# CarteTxCapteurDistance_2.net
KiCad netlist of a schematic drawn in Altium Designer
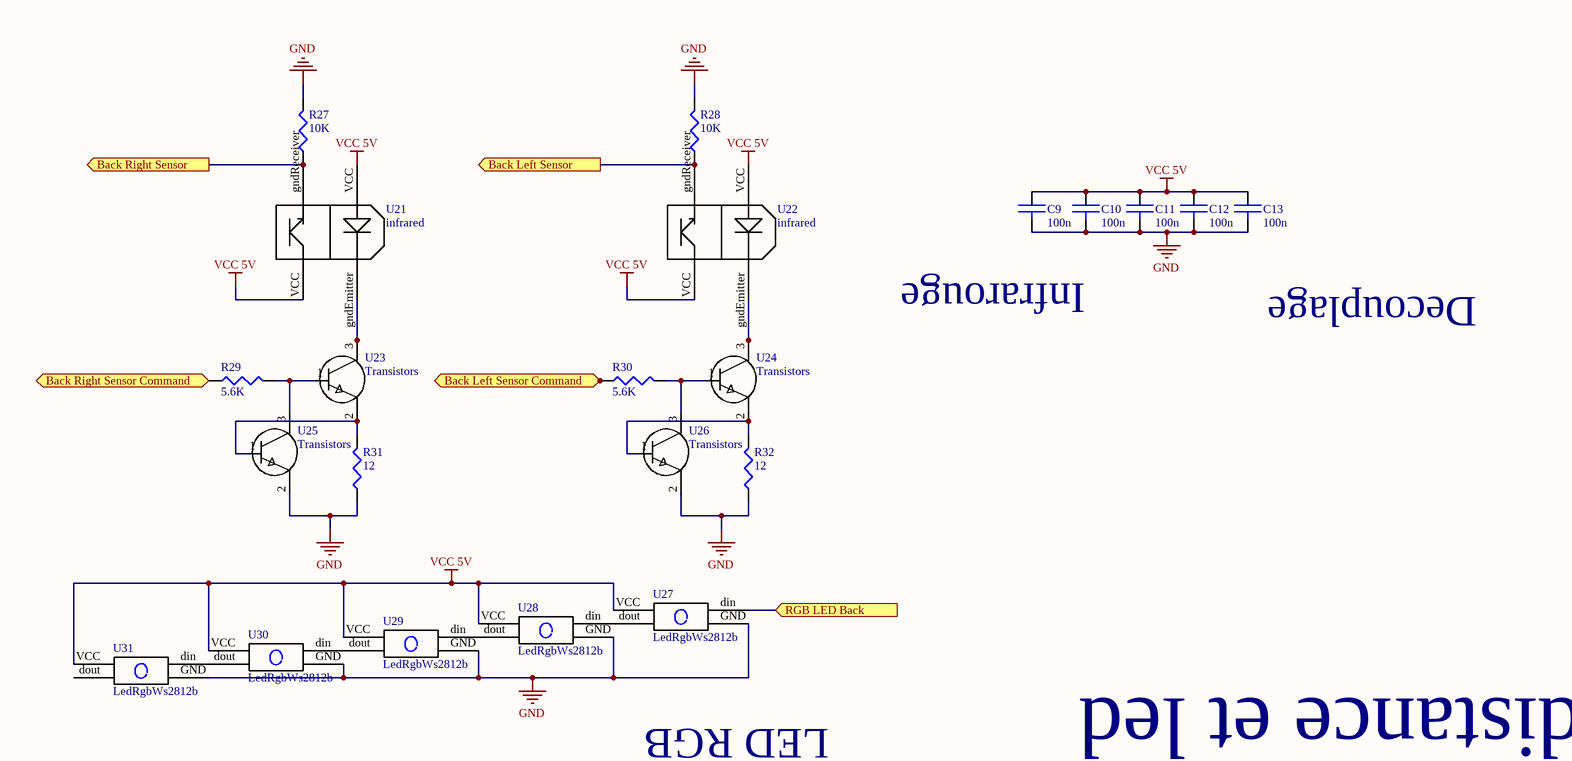
[diagram p0: CarteTxCapteurDistance 2.SchDoc, left]
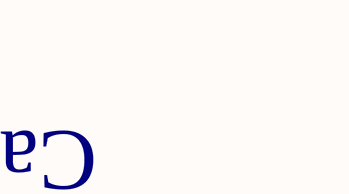
[diagram p1: CarteTxCapteurDistance 2.SchDoc, right]

(export (version "E")
  (design (tool "Eeschema 10.0.6"))
  (components
    (comp (ref "C9")
      (value "100n")
      (footprint "0805")
      (description "capacité non polarisée")
      (fields (field (name "Comment") "CAP"))
      (libsource (lib "ISEN_basics_26-05-2015") (part "CAP"))
    )
    (comp (ref "C10")
      (value "100n")
      (footprint "0805")
      (description "capacité non polarisée")
      (fields (field (name "Comment") "CAP"))
      (libsource (lib "ISEN_basics_26-05-2015") (part "CAP"))
    )
    (comp (ref "C11")
      (value "100n")
      (footprint "0805")
      (description "capacité non polarisée")
      (fields (field (name "Comment") "CAP"))
      (libsource (lib "ISEN_basics_26-05-2015") (part "CAP"))
    )
    (comp (ref "C12")
      (value "100n")
      (footprint "0805")
      (description "capacité non polarisée")
      (fields (field (name "Comment") "CAP"))
      (libsource (lib "ISEN_basics_26-05-2015") (part "CAP"))
    )
    (comp (ref "C13")
      (value "100n")
      (footprint "0805")
      (description "capacité non polarisée")
      (fields (field (name "Comment") "CAP"))
      (libsource (lib "ISEN_basics_26-05-2015") (part "CAP"))
    )
    (comp (ref "R27")
      (value "10K")
      (footprint "0805")
      (description "resistance")
      (fields (field (name "Comment") "RES"))
      (libsource (lib "ISEN_basics_26-05-2015") (part "RES"))
    )
    (comp (ref "R28")
      (value "10K")
      (footprint "0805")
      (description "resistance")
      (fields (field (name "Comment") "RES"))
      (libsource (lib "ISEN_basics_26-05-2015") (part "RES"))
    )
    (comp (ref "R29")
      (value "5.6K")
      (footprint "0805")
      (description "resistance")
      (fields (field (name "Comment") "RES"))
      (libsource (lib "ISEN_basics_26-05-2015") (part "RES"))
    )
    (comp (ref "R30")
      (value "5.6K")
      (footprint "0805")
      (description "resistance")
      (fields (field (name "Comment") "RES"))
      (libsource (lib "ISEN_basics_26-05-2015") (part "RES"))
    )
    (comp (ref "R31")
      (value "12")
      (footprint "0805")
      (description "resistance")
      (fields (field (name "Comment") "RES"))
      (libsource (lib "ISEN_basics_26-05-2015") (part "RES"))
    )
    (comp (ref "R32")
      (value "12")
      (footprint "0805")
      (description "resistance")
      (fields (field (name "Comment") "RES"))
      (libsource (lib "ISEN_basics_26-05-2015") (part "RES"))
    )
    (comp (ref "U21")
      (value "infrared")
      (footprint "Infrared")
      (libsource (lib "infrared") (part "RPR-359F"))
    )
    (comp (ref "U22")
      (value "infrared")
      (footprint "Infrared")
      (libsource (lib "infrared") (part "RPR-359F"))
    )
    (comp (ref "U23")
      (value "Transistors")
      (footprint "BC817-40")
      (description "NPN transistor")
      (libsource (lib "Transistors") (part "Transistors"))
    )
    (comp (ref "U24")
      (value "Transistors")
      (footprint "BC817-40")
      (description "NPN transistor")
      (libsource (lib "Transistors") (part "Transistors"))
    )
    (comp (ref "U25")
      (value "Transistors")
      (footprint "BC817-40")
      (description "NPN transistor")
      (libsource (lib "Transistors") (part "Transistors"))
    )
    (comp (ref "U26")
      (value "Transistors")
      (footprint "BC817-40")
      (description "NPN transistor")
      (libsource (lib "Transistors") (part "Transistors"))
    )
    (comp (ref "U27")
      (value "LedRgbWs2812b")
      (footprint "LedRgbWs2812b")
      (libsource (lib "LedRgbWs2812b") (part "LedRgbWs2812b"))
    )
    (comp (ref "U28")
      (value "LedRgbWs2812b")
      (footprint "LedRgbWs2812b")
      (libsource (lib "LedRgbWs2812b") (part "LedRgbWs2812b"))
    )
    (comp (ref "U29")
      (value "LedRgbWs2812b")
      (footprint "LedRgbWs2812b")
      (libsource (lib "LedRgbWs2812b") (part "LedRgbWs2812b"))
    )
    (comp (ref "U30")
      (value "LedRgbWs2812b")
      (footprint "LedRgbWs2812b")
      (libsource (lib "LedRgbWs2812b") (part "LedRgbWs2812b"))
    )
    (comp (ref "U31")
      (value "LedRgbWs2812b")
      (footprint "LedRgbWs2812b")
      (libsource (lib "LedRgbWs2812b") (part "LedRgbWs2812b"))
    )
  )
  (nets
    (net (code "1") (name "/Back Left Sensor") (class "Default")
      (node (ref "R28") (pin "1") (pintype "passive"))
      (node (ref "U22") (pin "gndReceiver") (pinfunction "gndReceiver_gndReceiver") (pintype "passive"))
    )
    (net (code "2") (name "/Back Left Sensor Command") (class "Default")
      (node (ref "R30") (pin "1") (pintype "passive"))
    )
    (net (code "3") (name "/Back Right Sensor") (class "Default")
      (node (ref "R27") (pin "1") (pintype "passive"))
      (node (ref "U21") (pin "gndReceiver") (pinfunction "gndReceiver_gndReceiver") (pintype "passive"))
    )
    (net (code "4") (name "/Back Right Sensor Command") (class "Default")
      (node (ref "R29") (pin "1") (pintype "passive"))
    )
    (net (code "5") (name "/RGB LED Back") (class "Default")
      (node (ref "U27") (pin "din") (pinfunction "din_din") (pintype "passive"))
    )
    (net (code "6") (name "GND") (class "Default")
      (node (ref "C10") (pin "2") (pinfunction "2_2") (pintype "passive"))
      (node (ref "C11") (pin "2") (pinfunction "2_2") (pintype "passive"))
      (node (ref "C12") (pin "2") (pinfunction "2_2") (pintype "passive"))
      (node (ref "C13") (pin "2") (pinfunction "2_2") (pintype "passive"))
      (node (ref "C9") (pin "2") (pinfunction "2_2") (pintype "passive"))
      (node (ref "R27") (pin "2") (pintype "passive"))
      (node (ref "R28") (pin "2") (pintype "passive"))
      (node (ref "R31") (pin "1") (pintype "passive"))
      (node (ref "R32") (pin "1") (pintype "passive"))
      (node (ref "U25") (pin "2") (pinfunction "Emi_2") (pintype "passive"))
      (node (ref "U26") (pin "2") (pinfunction "Emi_2") (pintype "passive"))
      (node (ref "U27") (pin "GND") (pinfunction "GND_GND") (pintype "passive"))
      (node (ref "U28") (pin "GND") (pinfunction "GND_GND") (pintype "passive"))
      (node (ref "U29") (pin "GND") (pinfunction "GND_GND") (pintype "passive"))
      (node (ref "U30") (pin "GND") (pinfunction "GND_GND") (pintype "passive"))
      (node (ref "U31") (pin "GND") (pinfunction "GND_GND") (pintype "passive"))
    )
    (net (code "7") (name "Net-(U23-Base)") (class "Default")
      (node (ref "R29") (pin "2") (pintype "passive"))
      (node (ref "U23") (pin "1") (pinfunction "Base_1") (pintype "passive"))
      (node (ref "U25") (pin "3") (pinfunction "Co_3") (pintype "passive"))
    )
    (net (code "8") (name "Net-(U23-Co)") (class "Default")
      (node (ref "U21") (pin "gndEmitter") (pinfunction "gndEmitter_gndEmitter") (pintype "passive"))
      (node (ref "U23") (pin "3") (pinfunction "Co_3") (pintype "passive"))
    )
    (net (code "9") (name "Net-(U23-Emi)") (class "Default")
      (node (ref "R31") (pin "2") (pintype "passive"))
      (node (ref "U23") (pin "2") (pinfunction "Emi_2") (pintype "passive"))
      (node (ref "U25") (pin "1") (pinfunction "Base_1") (pintype "passive"))
    )
    (net (code "10") (name "Net-(U24-Base)") (class "Default")
      (node (ref "R30") (pin "2") (pintype "passive"))
      (node (ref "U24") (pin "1") (pinfunction "Base_1") (pintype "passive"))
      (node (ref "U26") (pin "3") (pinfunction "Co_3") (pintype "passive"))
    )
    (net (code "11") (name "Net-(U24-Co)") (class "Default")
      (node (ref "U22") (pin "gndEmitter") (pinfunction "gndEmitter_gndEmitter") (pintype "passive"))
      (node (ref "U24") (pin "3") (pinfunction "Co_3") (pintype "passive"))
    )
    (net (code "12") (name "Net-(U24-Emi)") (class "Default")
      (node (ref "R32") (pin "2") (pintype "passive"))
      (node (ref "U24") (pin "2") (pinfunction "Emi_2") (pintype "passive"))
      (node (ref "U26") (pin "1") (pinfunction "Base_1") (pintype "passive"))
    )
    (net (code "13") (name "Net-(U27-Paddout)") (class "Default")
      (node (ref "U27") (pin "dout") (pinfunction "dout_dout") (pintype "passive"))
      (node (ref "U28") (pin "din") (pinfunction "din_din") (pintype "passive"))
    )
    (net (code "14") (name "Net-(U28-Paddout)") (class "Default")
      (node (ref "U28") (pin "dout") (pinfunction "dout_dout") (pintype "passive"))
      (node (ref "U29") (pin "din") (pinfunction "din_din") (pintype "passive"))
    )
    (net (code "15") (name "Net-(U29-Paddout)") (class "Default")
      (node (ref "U29") (pin "dout") (pinfunction "dout_dout") (pintype "passive"))
      (node (ref "U30") (pin "din") (pinfunction "din_din") (pintype "passive"))
    )
    (net (code "16") (name "Net-(U30-Paddout)") (class "Default")
      (node (ref "U30") (pin "dout") (pinfunction "dout_dout") (pintype "passive"))
      (node (ref "U31") (pin "din") (pinfunction "din_din") (pintype "passive"))
    )
    (net (code "17") (name "VCC 5V") (class "Default")
      (node (ref "C10") (pin "1") (pinfunction "1_1") (pintype "passive"))
      (node (ref "C11") (pin "1") (pinfunction "1_1") (pintype "passive"))
      (node (ref "C12") (pin "1") (pinfunction "1_1") (pintype "passive"))
      (node (ref "C13") (pin "1") (pinfunction "1_1") (pintype "passive"))
      (node (ref "C9") (pin "1") (pinfunction "1_1") (pintype "passive"))
      (node (ref "U21") (pin "VCC") (pinfunction "VCC_VCC") (pintype "passive"))
      (node (ref "U22") (pin "VCC") (pinfunction "VCC_VCC") (pintype "passive"))
      (node (ref "U27") (pin "VCC") (pinfunction "VCC_VCC") (pintype "passive"))
      (node (ref "U28") (pin "VCC") (pinfunction "VCC_VCC") (pintype "passive"))
      (node (ref "U29") (pin "VCC") (pinfunction "VCC_VCC") (pintype "passive"))
      (node (ref "U30") (pin "VCC") (pinfunction "VCC_VCC") (pintype "passive"))
      (node (ref "U31") (pin "VCC") (pinfunction "VCC_VCC") (pintype "passive"))
    )
    (net (code "18") (name "unconnected-(U31-Paddout)") (class "Default")
      (node (ref "U31") (pin "dout") (pinfunction "dout_dout") (pintype "passive"))
    )
  )
)
